# fpga-bank2.net
KiCad netlist of a schematic drawn in Altium Designer
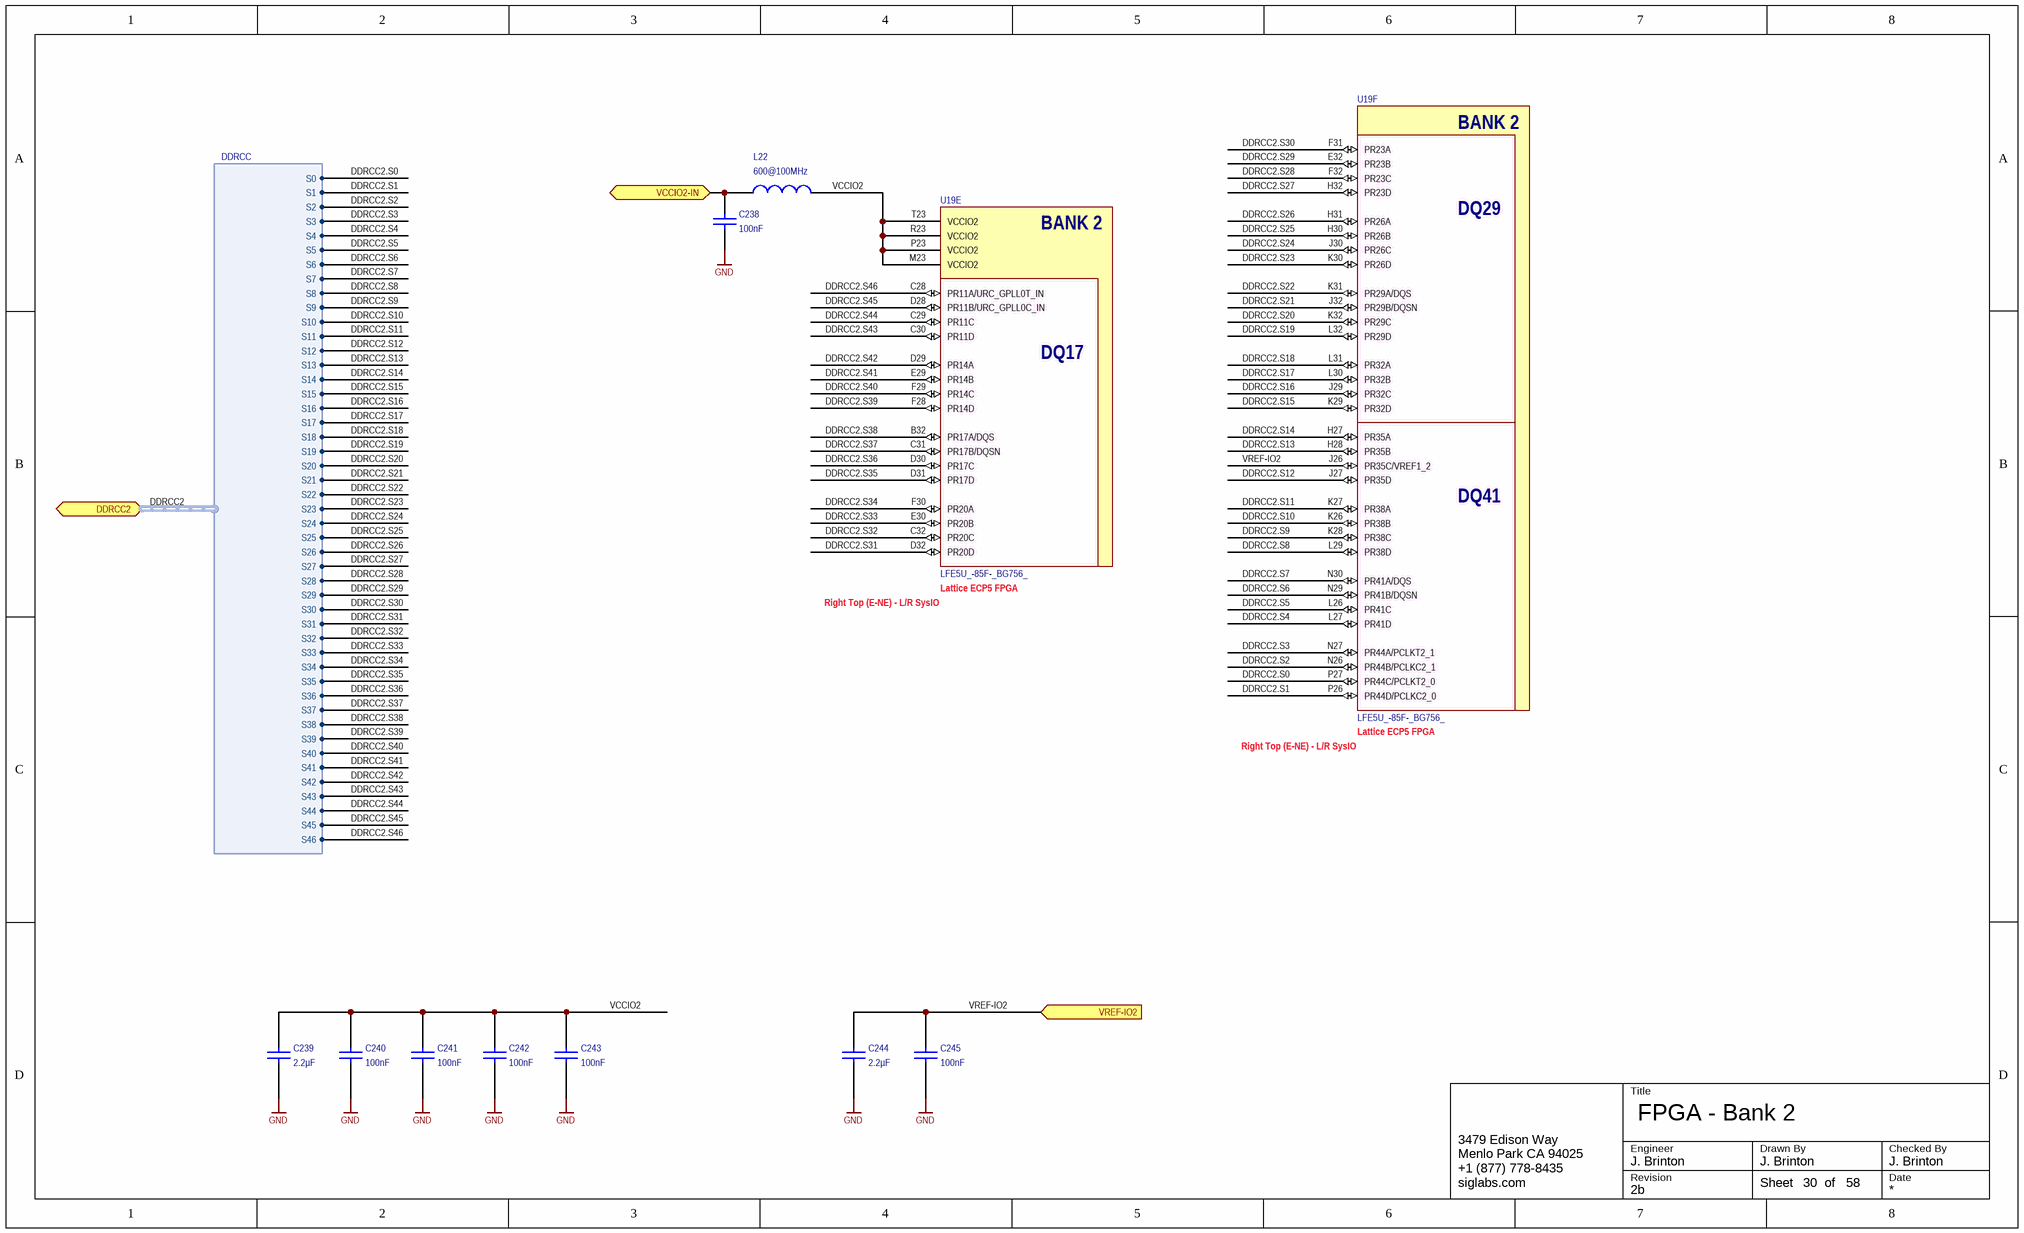
[diagram p0: fpga-bank2.SchDoc]

(export (version "E")
  (design (tool "Eeschema 10.0.6"))
  (components
    (comp (ref "C238")
      (value "100nF")
      (footprint "generic:CAPC1005X56N")
      (description "Ceramic Capacitor 100nF ±10% 16V X7R 0402")
      (fields (field (name "MANUFACTURER") "Murata") (field (name "TOLERANCE") "±10%"))
      (libsource (lib "murata") (part "GRM155R71A104KA01J"))
    )
    (comp (ref "C239")
      (value "2.2µF")
      (footprint "generic:CAPC1608X90N")
      (description "Ceramic Capacitor 2.2uF ±10% 10V X7R 0603")
      (fields (field (name "MANUFACTURER") "Murata") (field (name "TOLERANCE") "±10%"))
      (libsource (lib "murata") (part "GRM188R71A225KE15D"))
    )
    (comp (ref "C240")
      (value "100nF")
      (footprint "generic:CAPC1005X56N")
      (description "Ceramic Capacitor 100nF ±10% 16V X7R 0402")
      (fields (field (name "MANUFACTURER") "Murata") (field (name "TOLERANCE") "±10%"))
      (libsource (lib "murata") (part "GRM155R71A104KA01J"))
    )
    (comp (ref "C241")
      (value "100nF")
      (footprint "generic:CAPC1005X56N")
      (description "Ceramic Capacitor 100nF ±10% 16V X7R 0402")
      (fields (field (name "MANUFACTURER") "Murata") (field (name "TOLERANCE") "±10%"))
      (libsource (lib "murata") (part "GRM155R71A104KA01J"))
    )
    (comp (ref "C242")
      (value "100nF")
      (footprint "generic:CAPC1005X56N")
      (description "Ceramic Capacitor 100nF ±10% 16V X7R 0402")
      (fields (field (name "MANUFACTURER") "Murata") (field (name "TOLERANCE") "±10%"))
      (libsource (lib "murata") (part "GRM155R71A104KA01J"))
    )
    (comp (ref "C243")
      (value "100nF")
      (footprint "generic:CAPC1005X56N")
      (description "Ceramic Capacitor 100nF ±10% 16V X7R 0402")
      (fields (field (name "MANUFACTURER") "Murata") (field (name "TOLERANCE") "±10%"))
      (libsource (lib "murata") (part "GRM155R71A104KA01J"))
    )
    (comp (ref "C244")
      (value "2.2µF")
      (footprint "generic:CAPC1608X90N")
      (description "Ceramic Capacitor 2.2uF ±10% 10V X7R 0603")
      (fields (field (name "MANUFACTURER") "Murata") (field (name "TOLERANCE") "±10%"))
      (libsource (lib "murata") (part "GRM188R71A225KE15D"))
    )
    (comp (ref "C245")
      (value "100nF")
      (footprint "generic:CAPC1005X56N")
      (description "Ceramic Capacitor 100nF ±10% 16V X7R 0402")
      (fields (field (name "MANUFACTURER") "Murata") (field (name "TOLERANCE") "±10%"))
      (libsource (lib "murata") (part "GRM155R71A104KA01J"))
    )
    (comp (ref "L22")
      (value "600@100MHz")
      (footprint "0402")
      (description "Ferrite Bead 600-Ohm @ 100MHz 900mA 0402")
      (fields (field (name "MANUFACTURER") "Murata") (field (name "TOLERANCE") "±25%"))
      (libsource (lib "Graviton") (part "IND 0402"))
    )
    (comp (ref "U19")
      (value "LFE5U_-85F-_BG756_")
      (footprint "lattice:caBGA756")
      (description "ECP5 FPGA, 85k LUT, 756-caBGA")
      (fields (field (name "MANUFACTURER") "Lattice Semiconductor"))
      (libsource (lib "") (part "LFE5U_-85F-_BG756__1"))
    )
  )
  (nets
    (net (code "2") (name "/DDRCC2.S0") (class "Default")
      (node (ref "U19") (pin "P27") (pinfunction "PR44C/PCLKT2_0_P27") (pintype "bidirectional"))
    )
    (net (code "3") (name "/DDRCC2.S1") (class "Default")
      (node (ref "U19") (pin "P26") (pinfunction "PR44D/PCLKC2_0_P26") (pintype "bidirectional"))
    )
    (net (code "4") (name "/DDRCC2.S2") (class "Default")
      (node (ref "U19") (pin "N26") (pinfunction "PR44B/PCLKC2_1_N26") (pintype "bidirectional"))
    )
    (net (code "5") (name "/DDRCC2.S3") (class "Default")
      (node (ref "U19") (pin "N27") (pinfunction "PR44A/PCLKT2_1_N27") (pintype "bidirectional"))
    )
    (net (code "6") (name "/DDRCC2.S4") (class "Default")
      (node (ref "U19") (pin "L27") (pinfunction "PR41D_L27") (pintype "bidirectional"))
    )
    (net (code "7") (name "/DDRCC2.S5") (class "Default")
      (node (ref "U19") (pin "L26") (pinfunction "PR41C_L26") (pintype "bidirectional"))
    )
    (net (code "8") (name "/DDRCC2.S6") (class "Default")
      (node (ref "U19") (pin "N29") (pinfunction "PR41B/DQSN_N29") (pintype "bidirectional"))
    )
    (net (code "9") (name "/DDRCC2.S7") (class "Default")
      (node (ref "U19") (pin "N30") (pinfunction "PR41A/DQS_N30") (pintype "bidirectional"))
    )
    (net (code "10") (name "/DDRCC2.S8") (class "Default")
      (node (ref "U19") (pin "L29") (pinfunction "PR38D_L29") (pintype "bidirectional"))
    )
    (net (code "11") (name "/DDRCC2.S9") (class "Default")
      (node (ref "U19") (pin "K28") (pinfunction "PR38C_K28") (pintype "bidirectional"))
    )
    (net (code "12") (name "/DDRCC2.S10") (class "Default")
      (node (ref "U19") (pin "K26") (pinfunction "PR38B_K26") (pintype "bidirectional"))
    )
    (net (code "13") (name "/DDRCC2.S11") (class "Default")
      (node (ref "U19") (pin "K27") (pinfunction "PR38A_K27") (pintype "bidirectional"))
    )
    (net (code "14") (name "/DDRCC2.S12") (class "Default")
      (node (ref "U19") (pin "J27") (pinfunction "PR35D_J27") (pintype "bidirectional"))
    )
    (net (code "15") (name "/DDRCC2.S13") (class "Default")
      (node (ref "U19") (pin "H28") (pinfunction "PR35B_H28") (pintype "bidirectional"))
    )
    (net (code "16") (name "/DDRCC2.S14") (class "Default")
      (node (ref "U19") (pin "H27") (pinfunction "PR35A_H27") (pintype "bidirectional"))
    )
    (net (code "17") (name "/DDRCC2.S15") (class "Default")
      (node (ref "U19") (pin "K29") (pinfunction "PR32D_K29") (pintype "bidirectional"))
    )
    (net (code "18") (name "/DDRCC2.S16") (class "Default")
      (node (ref "U19") (pin "J29") (pinfunction "PR32C_J29") (pintype "bidirectional"))
    )
    (net (code "19") (name "/DDRCC2.S17") (class "Default")
      (node (ref "U19") (pin "L30") (pinfunction "PR32B_L30") (pintype "bidirectional"))
    )
    (net (code "20") (name "/DDRCC2.S18") (class "Default")
      (node (ref "U19") (pin "L31") (pinfunction "PR32A_L31") (pintype "bidirectional"))
    )
    (net (code "21") (name "/DDRCC2.S19") (class "Default")
      (node (ref "U19") (pin "L32") (pinfunction "PR29D_L32") (pintype "bidirectional"))
    )
    (net (code "22") (name "/DDRCC2.S20") (class "Default")
      (node (ref "U19") (pin "K32") (pinfunction "PR29C_K32") (pintype "bidirectional"))
    )
    (net (code "23") (name "/DDRCC2.S21") (class "Default")
      (node (ref "U19") (pin "J32") (pinfunction "PR29B/DQSN_J32") (pintype "bidirectional"))
    )
    (net (code "24") (name "/DDRCC2.S22") (class "Default")
      (node (ref "U19") (pin "K31") (pinfunction "PR29A/DQS_K31") (pintype "bidirectional"))
    )
    (net (code "25") (name "/DDRCC2.S23") (class "Default")
      (node (ref "U19") (pin "K30") (pinfunction "PR26D_K30") (pintype "bidirectional"))
    )
    (net (code "26") (name "/DDRCC2.S24") (class "Default")
      (node (ref "U19") (pin "J30") (pinfunction "PR26C_J30") (pintype "bidirectional"))
    )
    (net (code "27") (name "/DDRCC2.S25") (class "Default")
      (node (ref "U19") (pin "H30") (pinfunction "PR26B_H30") (pintype "bidirectional"))
    )
    (net (code "28") (name "/DDRCC2.S26") (class "Default")
      (node (ref "U19") (pin "H31") (pinfunction "PR26A_H31") (pintype "bidirectional"))
    )
    (net (code "29") (name "/DDRCC2.S27") (class "Default")
      (node (ref "U19") (pin "H32") (pinfunction "PR23D_H32") (pintype "bidirectional"))
    )
    (net (code "30") (name "/DDRCC2.S28") (class "Default")
      (node (ref "U19") (pin "F32") (pinfunction "PR23C_F32") (pintype "bidirectional"))
    )
    (net (code "31") (name "/DDRCC2.S29") (class "Default")
      (node (ref "U19") (pin "E32") (pinfunction "PR23B_E32") (pintype "bidirectional"))
    )
    (net (code "32") (name "/DDRCC2.S30") (class "Default")
      (node (ref "U19") (pin "F31") (pinfunction "PR23A_F31") (pintype "bidirectional"))
    )
    (net (code "33") (name "/DDRCC2.S31") (class "Default")
      (node (ref "U19") (pin "D32") (pinfunction "PR20D_D32") (pintype "bidirectional"))
    )
    (net (code "34") (name "/DDRCC2.S32") (class "Default")
      (node (ref "U19") (pin "C32") (pinfunction "PR20C_C32") (pintype "bidirectional"))
    )
    (net (code "35") (name "/DDRCC2.S33") (class "Default")
      (node (ref "U19") (pin "E30") (pinfunction "PR20B_E30") (pintype "bidirectional"))
    )
    (net (code "36") (name "/DDRCC2.S34") (class "Default")
      (node (ref "U19") (pin "F30") (pinfunction "PR20A_F30") (pintype "bidirectional"))
    )
    (net (code "37") (name "/DDRCC2.S35") (class "Default")
      (node (ref "U19") (pin "D31") (pinfunction "PR17D_D31") (pintype "bidirectional"))
    )
    (net (code "38") (name "/DDRCC2.S36") (class "Default")
      (node (ref "U19") (pin "D30") (pinfunction "PR17C_D30") (pintype "bidirectional"))
    )
    (net (code "39") (name "/DDRCC2.S37") (class "Default")
      (node (ref "U19") (pin "C31") (pinfunction "PR17B/DQSN_C31") (pintype "bidirectional"))
    )
    (net (code "40") (name "/DDRCC2.S38") (class "Default")
      (node (ref "U19") (pin "B32") (pinfunction "PR17A/DQS_B32") (pintype "bidirectional"))
    )
    (net (code "41") (name "/DDRCC2.S39") (class "Default")
      (node (ref "U19") (pin "F28") (pinfunction "PR14D_F28") (pintype "bidirectional"))
    )
    (net (code "42") (name "/DDRCC2.S40") (class "Default")
      (node (ref "U19") (pin "F29") (pinfunction "PR14C_F29") (pintype "bidirectional"))
    )
    (net (code "43") (name "/DDRCC2.S41") (class "Default")
      (node (ref "U19") (pin "E29") (pinfunction "PR14B_E29") (pintype "bidirectional"))
    )
    (net (code "44") (name "/DDRCC2.S42") (class "Default")
      (node (ref "U19") (pin "D29") (pinfunction "PR14A_D29") (pintype "bidirectional"))
    )
    (net (code "45") (name "/DDRCC2.S43") (class "Default")
      (node (ref "U19") (pin "C30") (pinfunction "PR11D_C30") (pintype "bidirectional"))
    )
    (net (code "46") (name "/DDRCC2.S44") (class "Default")
      (node (ref "U19") (pin "C29") (pinfunction "PR11C_C29") (pintype "bidirectional"))
    )
    (net (code "47") (name "/DDRCC2.S45") (class "Default")
      (node (ref "U19") (pin "D28") (pinfunction "PR11B/URC_GPLL0C_IN_D28") (pintype "bidirectional"))
    )
    (net (code "48") (name "/DDRCC2.S46") (class "Default")
      (node (ref "U19") (pin "C28") (pinfunction "PR11A/URC_GPLL0T_IN_C28") (pintype "bidirectional"))
    )
    (net (code "50") (name "/VCCIO2") (class "Default")
      (node (ref "C239") (pin "2") (pinfunction "2_2") (pintype "passive"))
      (node (ref "C240") (pin "2") (pinfunction "2_2") (pintype "passive"))
      (node (ref "C241") (pin "2") (pinfunction "2_2") (pintype "passive"))
      (node (ref "C242") (pin "2") (pinfunction "2_2") (pintype "passive"))
      (node (ref "C243") (pin "2") (pinfunction "2_2") (pintype "passive"))
      (node (ref "L22") (pin "1") (pinfunction "1_1") (pintype "passive"))
      (node (ref "U19") (pin "M23") (pinfunction "VCCIO2_M23") (pintype "power_in"))
      (node (ref "U19") (pin "P23") (pinfunction "VCCIO2_P23") (pintype "power_in"))
      (node (ref "U19") (pin "R23") (pinfunction "VCCIO2_R23") (pintype "power_in"))
      (node (ref "U19") (pin "T23") (pinfunction "VCCIO2_T23") (pintype "power_in"))
    )
    (net (code "51") (name "/VCCIO2-IN") (class "Default")
      (node (ref "C238") (pin "2") (pinfunction "2_2") (pintype "passive"))
      (node (ref "L22") (pin "2") (pinfunction "2_2") (pintype "passive"))
    )
    (net (code "52") (name "/VREF-IO2") (class "Default")
      (node (ref "C244") (pin "2") (pinfunction "2_2") (pintype "passive"))
      (node (ref "C245") (pin "2") (pinfunction "2_2") (pintype "passive"))
      (node (ref "U19") (pin "J26") (pinfunction "PR35C/VREF1_2_J26") (pintype "bidirectional"))
    )
    (net (code "53") (name "GND") (class "Default")
      (node (ref "C238") (pin "1") (pinfunction "1_1") (pintype "passive"))
      (node (ref "C239") (pin "1") (pinfunction "1_1") (pintype "passive"))
      (node (ref "C240") (pin "1") (pinfunction "1_1") (pintype "passive"))
      (node (ref "C241") (pin "1") (pinfunction "1_1") (pintype "passive"))
      (node (ref "C242") (pin "1") (pinfunction "1_1") (pintype "passive"))
      (node (ref "C243") (pin "1") (pinfunction "1_1") (pintype "passive"))
      (node (ref "C244") (pin "1") (pinfunction "1_1") (pintype "passive"))
      (node (ref "C245") (pin "1") (pinfunction "1_1") (pintype "passive"))
    )
  )
)
